# module-si1133.net
KiCad netlist of a schematic drawn in EAGLE
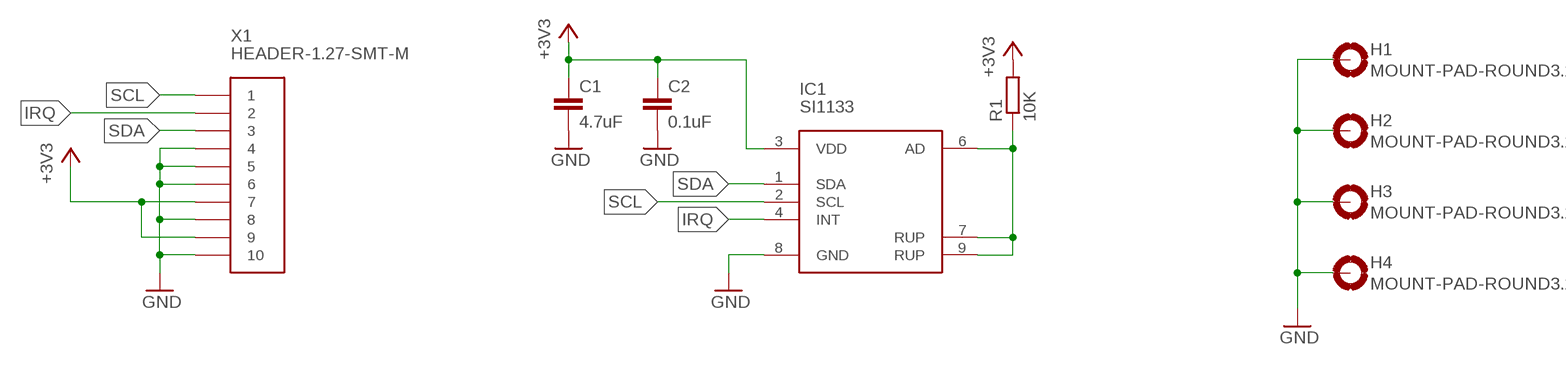
[diagram p0: schematic, sheet 1]

(export (version "E")
  (design (tool "Eeschema 10.0.6"))
  (components
    (comp (ref "C1")
      (value "4.7uF")
      (footprint "eagle-import:C0805")
      (libsource (lib "eagle-import") (part "C-EUC0805"))
    )
    (comp (ref "C2")
      (value "0.1uF")
      (footprint "eagle-import:C0603")
      (libsource (lib "eagle-import") (part "C-EUC0603"))
    )
    (comp (ref "H1")
      (value "MOUNT-PAD-ROUND3.2")
      (footprint "eagle-import:3,2-PAD")
      (libsource (lib "eagle-import") (part "MOUNT-PAD-ROUND3.2"))
    )
    (comp (ref "H2")
      (value "MOUNT-PAD-ROUND3.2")
      (footprint "eagle-import:3,2-PAD")
      (libsource (lib "eagle-import") (part "MOUNT-PAD-ROUND3.2"))
    )
    (comp (ref "H3")
      (value "MOUNT-PAD-ROUND3.2")
      (footprint "eagle-import:3,2-PAD")
      (libsource (lib "eagle-import") (part "MOUNT-PAD-ROUND3.2"))
    )
    (comp (ref "H4")
      (value "MOUNT-PAD-ROUND3.2")
      (footprint "eagle-import:3,2-PAD")
      (libsource (lib "eagle-import") (part "MOUNT-PAD-ROUND3.2"))
    )
    (comp (ref "IC1")
      (value "SI1133")
      (footprint "eagle-import:DFN10-2X2")
      (libsource (lib "eagle-import") (part "SI1133"))
    )
    (comp (ref "R1")
      (value "10K")
      (footprint "eagle-import:R0603")
      (libsource (lib "eagle-import") (part "R-EU_R0603"))
    )
    (comp (ref "X1")
      (value "HEADER-1.27-SMT-M")
      (footprint "eagle-import:HEADER-1.27-SMT-M")
      (libsource (lib "eagle-import") (part "HEADER-1.27-SMT-M"))
    )
  )
  (nets
    (net (code "1") (name "+3V3") (class "Default")
      (node (ref "C1") (pin "1") (pinfunction "1_1") (pintype "passive"))
      (node (ref "C2") (pin "1") (pinfunction "1_1") (pintype "passive"))
      (node (ref "IC1") (pin "3") (pinfunction "VDD_3") (pintype "bidirectional"))
      (node (ref "R1") (pin "2") (pinfunction "2_2") (pintype "passive"))
      (node (ref "X1") (pin "7") (pinfunction "7_7") (pintype "bidirectional"))
      (node (ref "X1") (pin "9") (pinfunction "9_9") (pintype "bidirectional"))
    )
    (net (code "2") (name "GND") (class "Default")
      (node (ref "C1") (pin "2") (pinfunction "2_2") (pintype "passive"))
      (node (ref "C2") (pin "2") (pinfunction "2_2") (pintype "passive"))
      (node (ref "H1") (pin "B3,2") (pinfunction "MOUNT_B3,2") (pintype "passive"))
      (node (ref "H2") (pin "B3,2") (pinfunction "MOUNT_B3,2") (pintype "passive"))
      (node (ref "H3") (pin "B3,2") (pinfunction "MOUNT_B3,2") (pintype "passive"))
      (node (ref "H4") (pin "B3,2") (pinfunction "MOUNT_B3,2") (pintype "passive"))
      (node (ref "IC1") (pin "8") (pinfunction "GND_8") (pintype "bidirectional"))
      (node (ref "X1") (pin "10") (pinfunction "10_10") (pintype "bidirectional"))
      (node (ref "X1") (pin "4") (pinfunction "4_4") (pintype "bidirectional"))
      (node (ref "X1") (pin "5") (pinfunction "5_5") (pintype "bidirectional"))
      (node (ref "X1") (pin "6") (pinfunction "6_6") (pintype "bidirectional"))
      (node (ref "X1") (pin "8") (pinfunction "8_8") (pintype "bidirectional"))
    )
    (net (code "3") (name "IRQ") (class "Default")
      (node (ref "IC1") (pin "4") (pinfunction "INT_4") (pintype "bidirectional"))
      (node (ref "X1") (pin "2") (pinfunction "2_2") (pintype "bidirectional"))
    )
    (net (code "4") (name "Net-(IC1-AD)") (class "Default")
      (node (ref "IC1") (pin "6") (pinfunction "AD_6") (pintype "bidirectional"))
      (node (ref "IC1") (pin "7") (pinfunction "RUP_7") (pintype "bidirectional"))
      (node (ref "IC1") (pin "9") (pinfunction "RUP_9") (pintype "bidirectional"))
      (node (ref "R1") (pin "1") (pinfunction "1_1") (pintype "passive"))
    )
    (net (code "5") (name "SCL") (class "Default")
      (node (ref "IC1") (pin "2") (pinfunction "SCL_2") (pintype "bidirectional"))
      (node (ref "X1") (pin "1") (pinfunction "1_1") (pintype "bidirectional"))
    )
    (net (code "6") (name "SDA") (class "Default")
      (node (ref "IC1") (pin "1") (pinfunction "SDA_1") (pintype "bidirectional"))
      (node (ref "X1") (pin "3") (pinfunction "3_3") (pintype "bidirectional"))
    )
  )
)
